# Root1_Interfaces_Test.net
KiCad netlist of a schematic drawn in EAGLE
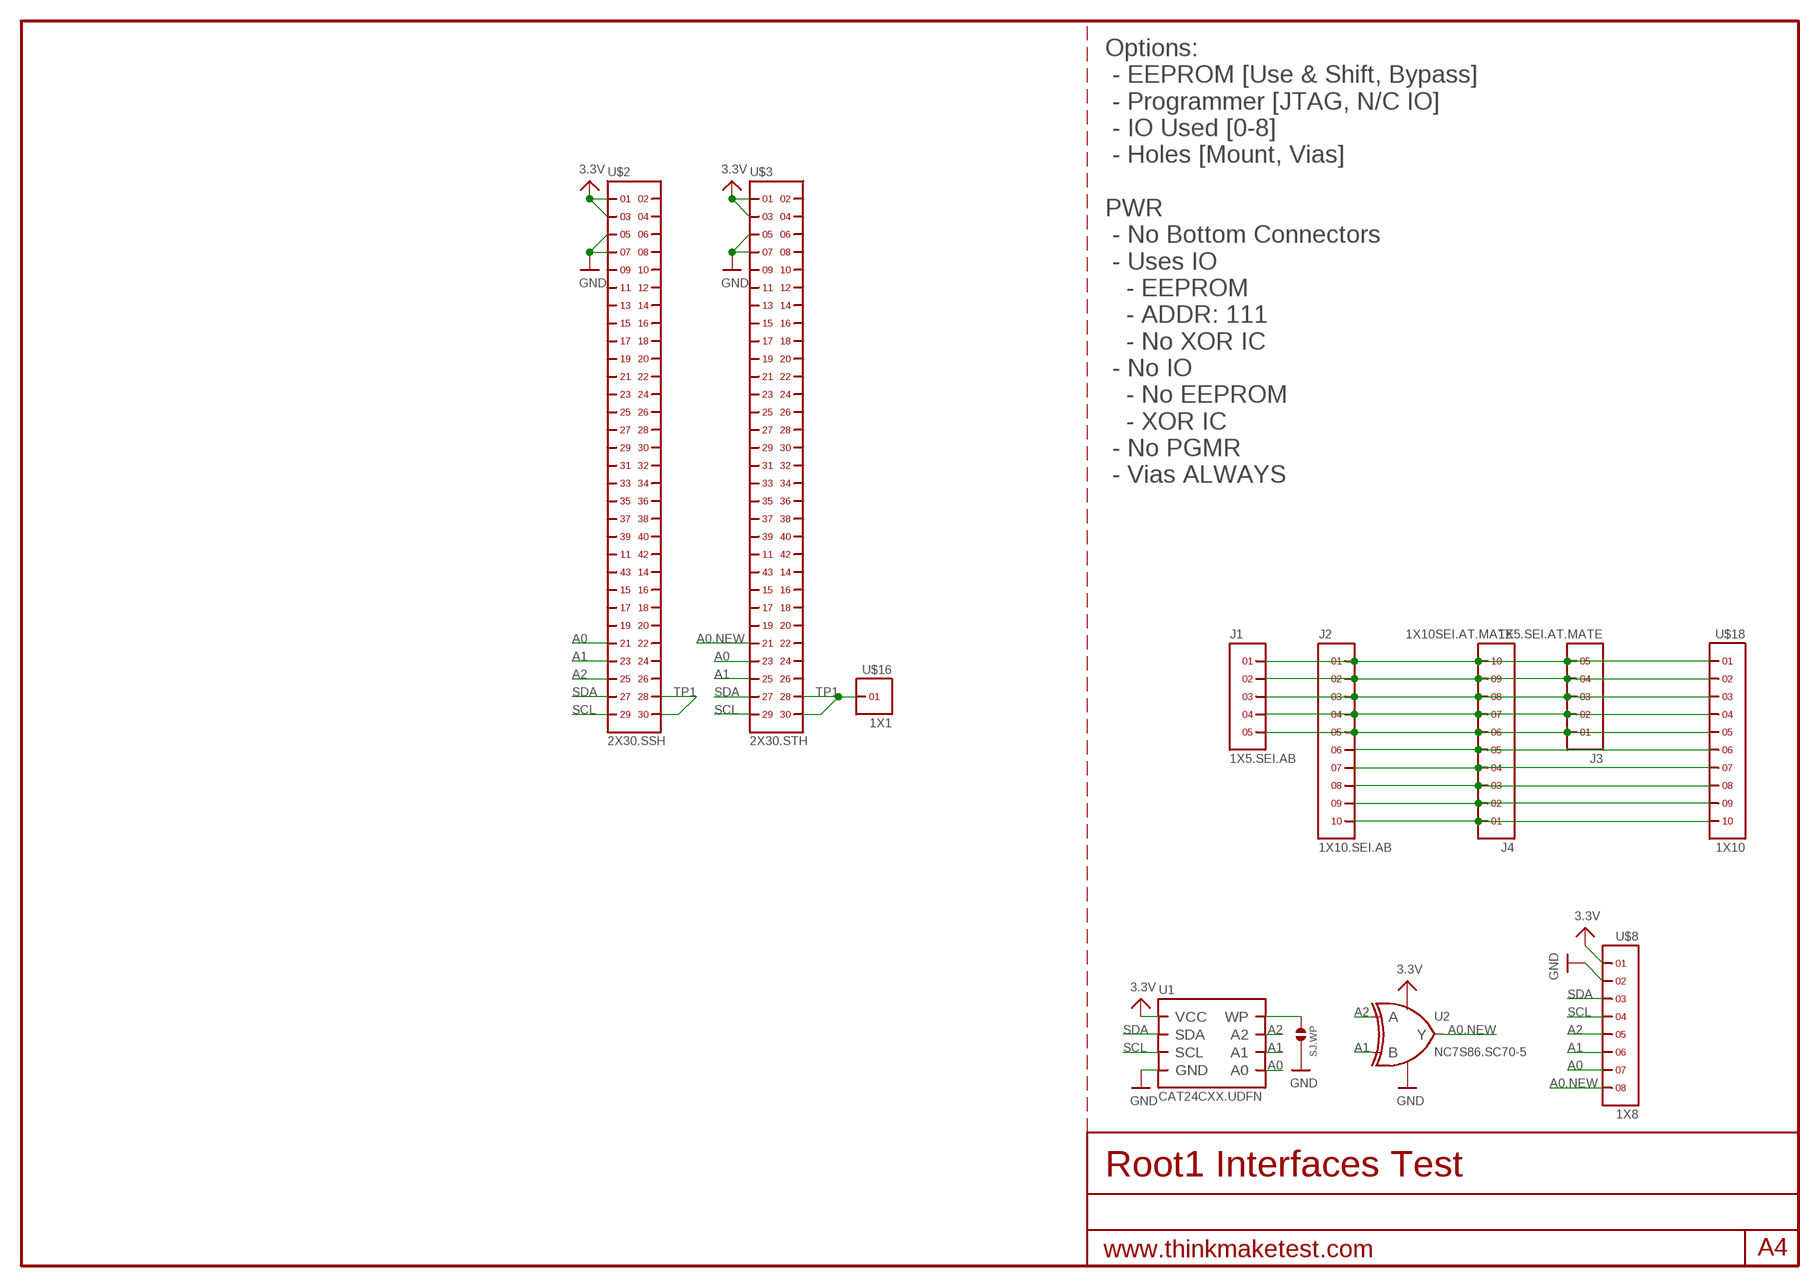
[diagram p0: schematic, sheet 1]

(export (version "E")
  (design (tool "Eeschema 10.0.6"))
  (components
    (comp (ref "J1")
      (value "1X5.SEI.AB")
      (footprint "eagle-import:SEI-105-02-XX-S-X-AB")
      (libsource (lib "eagle-import") (part "1X5.SEI.AB"))
    )
    (comp (ref "J2")
      (value "1X10.SEI.AB")
      (footprint "eagle-import:SEI-110-02-XX-S-X-AB")
      (libsource (lib "eagle-import") (part "1X10.SEI.AB"))
    )
    (comp (ref "J3")
      (value "1X5.SEI.AT.MATE")
      (footprint "eagle-import:SEI-105-02-XX-S-AT.MATE")
      (libsource (lib "eagle-import") (part "1X5.SEI.AT.MATE"))
    )
    (comp (ref "J4")
      (value "1X10SEI.AT.MATE")
      (footprint "eagle-import:SEI-110-02-XX-S-X-AT.MATE")
      (libsource (lib "eagle-import") (part "1X10SEI.AT.MATE"))
    )
    (comp (ref "SJ.WP")
      (value "SOLDERJUMPER.2.MED")
      (footprint "eagle-import:2.MED")
      (libsource (lib "eagle-import") (part "SOLDERJUMPER.2.MED"))
    )
    (comp (ref "U$2")
      (value "2X30.SSH")
      (footprint "eagle-import:SSH-030-X.XX-X-D-A")
      (libsource (lib "eagle-import") (part "2X30.SSH"))
    )
    (comp (ref "U$3")
      (value "2X30.STH")
      (footprint "eagle-import:STH-030-X.XX-X-D-A")
      (libsource (lib "eagle-import") (part "2X30.STH"))
    )
    (comp (ref "U$8")
      (value "1X8")
      (footprint "eagle-import:1X8")
      (libsource (lib "eagle-import") (part "1X8"))
    )
    (comp (ref "U$16")
      (value "1X1")
      (footprint "eagle-import:1X1")
      (libsource (lib "eagle-import") (part "1X1"))
    )
    (comp (ref "U$18")
      (value "1X10")
      (footprint "eagle-import:1X10")
      (libsource (lib "eagle-import") (part "1X10"))
    )
    (comp (ref "U1")
      (value "CAT24CXX.UDFN")
      (footprint "eagle-import:UDFN8.2X3MM")
      (libsource (lib "eagle-import") (part "CAT24CXX.UDFN"))
    )
    (comp (ref "U2")
      (value "NC7S86.SC70-5")
      (footprint "eagle-import:SC70-5")
      (libsource (lib "eagle-import") (part "NC7S86.SC70-5"))
    )
  )
  (nets
    (net (code "1") (name "/A0") (class "Default")
      (node (ref "U$2") (pin "51") (pinfunction "51_51") (pintype "bidirectional"))
      (node (ref "U$3") (pin "53") (pinfunction "53_53") (pintype "bidirectional"))
      (node (ref "U$8") (pin "7") (pinfunction "7_7") (pintype "bidirectional"))
      (node (ref "U1") (pin "1") (pinfunction "A0_1") (pintype "bidirectional"))
    )
    (net (code "2") (name "/A0.NEW") (class "Default")
      (node (ref "U$3") (pin "51") (pinfunction "51_51") (pintype "bidirectional"))
      (node (ref "U$8") (pin "8") (pinfunction "8_8") (pintype "bidirectional"))
      (node (ref "U2") (pin "4") (pinfunction "Y_4") (pintype "bidirectional"))
    )
    (net (code "3") (name "/A1") (class "Default")
      (node (ref "U$2") (pin "53") (pinfunction "53_53") (pintype "bidirectional"))
      (node (ref "U$3") (pin "55") (pinfunction "55_55") (pintype "bidirectional"))
      (node (ref "U$8") (pin "6") (pinfunction "6_6") (pintype "bidirectional"))
      (node (ref "U1") (pin "2") (pinfunction "A1_2") (pintype "bidirectional"))
      (node (ref "U2") (pin "2") (pinfunction "B_2") (pintype "bidirectional"))
    )
    (net (code "4") (name "/A2") (class "Default")
      (node (ref "U$2") (pin "55") (pinfunction "55_55") (pintype "bidirectional"))
      (node (ref "U$8") (pin "5") (pinfunction "5_5") (pintype "bidirectional"))
      (node (ref "U1") (pin "3") (pinfunction "A2_3") (pintype "bidirectional"))
      (node (ref "U2") (pin "1") (pinfunction "A_1") (pintype "bidirectional"))
    )
    (net (code "5") (name "/SCL") (class "Default")
      (node (ref "U$2") (pin "59") (pinfunction "59_59") (pintype "bidirectional"))
      (node (ref "U$3") (pin "59") (pinfunction "59_59") (pintype "bidirectional"))
      (node (ref "U$8") (pin "4") (pinfunction "4_4") (pintype "bidirectional"))
      (node (ref "U1") (pin "6") (pinfunction "SCL_6") (pintype "bidirectional"))
    )
    (net (code "6") (name "/SDA") (class "Default")
      (node (ref "U$2") (pin "57") (pinfunction "57_57") (pintype "bidirectional"))
      (node (ref "U$3") (pin "57") (pinfunction "57_57") (pintype "bidirectional"))
      (node (ref "U$8") (pin "3") (pinfunction "3_3") (pintype "bidirectional"))
      (node (ref "U1") (pin "5") (pinfunction "SDA_5") (pintype "bidirectional"))
    )
    (net (code "7") (name "/TP1") (class "Default")
      (node (ref "U$16") (pin "1") (pinfunction "1_1") (pintype "bidirectional"))
      (node (ref "U$2") (pin "58") (pinfunction "58_58") (pintype "bidirectional"))
      (node (ref "U$2") (pin "60") (pinfunction "60_60") (pintype "bidirectional"))
      (node (ref "U$3") (pin "58") (pinfunction "58_58") (pintype "bidirectional"))
      (node (ref "U$3") (pin "60") (pinfunction "60_60") (pintype "bidirectional"))
    )
    (net (code "8") (name "3.3V") (class "Default")
      (node (ref "U$2") (pin "1") (pinfunction "1_1") (pintype "bidirectional"))
      (node (ref "U$2") (pin "3") (pinfunction "3_3") (pintype "bidirectional"))
      (node (ref "U$3") (pin "1") (pinfunction "1_1") (pintype "bidirectional"))
      (node (ref "U$3") (pin "3") (pinfunction "3_3") (pintype "bidirectional"))
      (node (ref "U$8") (pin "1") (pinfunction "1_1") (pintype "bidirectional"))
      (node (ref "U1") (pin "8") (pinfunction "VCC_8") (pintype "bidirectional"))
      (node (ref "U2") (pin "6") (pinfunction "VCC_6") (pintype "bidirectional"))
    )
    (net (code "9") (name "GND") (class "Default")
      (node (ref "SJ.WP") (pin "2") (pinfunction "2_2") (pintype "bidirectional"))
      (node (ref "U$2") (pin "5") (pinfunction "5_5") (pintype "bidirectional"))
      (node (ref "U$2") (pin "7") (pinfunction "7_7") (pintype "bidirectional"))
      (node (ref "U$3") (pin "5") (pinfunction "5_5") (pintype "bidirectional"))
      (node (ref "U$3") (pin "7") (pinfunction "7_7") (pintype "bidirectional"))
      (node (ref "U$8") (pin "2") (pinfunction "2_2") (pintype "bidirectional"))
      (node (ref "U1") (pin "4") (pinfunction "GND_4") (pintype "bidirectional"))
      (node (ref "U1") (pin "PAD") (pinfunction "GND_PAD") (pintype "bidirectional"))
      (node (ref "U2") (pin "3") (pinfunction "GND_3") (pintype "bidirectional"))
    )
    (net (code "10") (name "Net-(J1-Pad1)") (class "Default")
      (node (ref "J1") (pin "1") (pinfunction "1_1") (pintype "bidirectional"))
      (node (ref "J2") (pin "1") (pinfunction "1_1") (pintype "bidirectional"))
      (node (ref "J3") (pin "5") (pinfunction "5_5") (pintype "bidirectional"))
      (node (ref "J4") (pin "10") (pinfunction "10_10") (pintype "bidirectional"))
      (node (ref "U$18") (pin "1") (pinfunction "1_1") (pintype "bidirectional"))
    )
    (net (code "11") (name "Net-(J1-Pad2)") (class "Default")
      (node (ref "J1") (pin "2") (pinfunction "2_2") (pintype "bidirectional"))
      (node (ref "J2") (pin "2") (pinfunction "2_2") (pintype "bidirectional"))
      (node (ref "J3") (pin "4") (pinfunction "4_4") (pintype "bidirectional"))
      (node (ref "J4") (pin "9") (pinfunction "9_9") (pintype "bidirectional"))
      (node (ref "U$18") (pin "2") (pinfunction "2_2") (pintype "bidirectional"))
    )
    (net (code "12") (name "Net-(J1-Pad3)") (class "Default")
      (node (ref "J1") (pin "3") (pinfunction "3_3") (pintype "bidirectional"))
      (node (ref "J2") (pin "3") (pinfunction "3_3") (pintype "bidirectional"))
      (node (ref "J3") (pin "3") (pinfunction "3_3") (pintype "bidirectional"))
      (node (ref "J4") (pin "8") (pinfunction "8_8") (pintype "bidirectional"))
      (node (ref "U$18") (pin "3") (pinfunction "3_3") (pintype "bidirectional"))
    )
    (net (code "13") (name "Net-(J1-Pad4)") (class "Default")
      (node (ref "J1") (pin "4") (pinfunction "4_4") (pintype "bidirectional"))
      (node (ref "J2") (pin "4") (pinfunction "4_4") (pintype "bidirectional"))
      (node (ref "J3") (pin "2") (pinfunction "2_2") (pintype "bidirectional"))
      (node (ref "J4") (pin "7") (pinfunction "7_7") (pintype "bidirectional"))
      (node (ref "U$18") (pin "4") (pinfunction "4_4") (pintype "bidirectional"))
    )
    (net (code "14") (name "Net-(J1-Pad5)") (class "Default")
      (node (ref "J1") (pin "5") (pinfunction "5_5") (pintype "bidirectional"))
      (node (ref "J2") (pin "5") (pinfunction "5_5") (pintype "bidirectional"))
      (node (ref "J3") (pin "1") (pinfunction "1_1") (pintype "bidirectional"))
      (node (ref "J4") (pin "6") (pinfunction "6_6") (pintype "bidirectional"))
      (node (ref "U$18") (pin "5") (pinfunction "5_5") (pintype "bidirectional"))
    )
    (net (code "15") (name "Net-(J2-Pad6)") (class "Default")
      (node (ref "J2") (pin "6") (pinfunction "6_6") (pintype "bidirectional"))
      (node (ref "J4") (pin "5") (pinfunction "5_5") (pintype "bidirectional"))
      (node (ref "U$18") (pin "6") (pinfunction "6_6") (pintype "bidirectional"))
    )
    (net (code "16") (name "Net-(J2-Pad7)") (class "Default")
      (node (ref "J2") (pin "7") (pinfunction "7_7") (pintype "bidirectional"))
      (node (ref "J4") (pin "4") (pinfunction "4_4") (pintype "bidirectional"))
      (node (ref "U$18") (pin "7") (pinfunction "7_7") (pintype "bidirectional"))
    )
    (net (code "17") (name "Net-(J2-Pad8)") (class "Default")
      (node (ref "J2") (pin "8") (pinfunction "8_8") (pintype "bidirectional"))
      (node (ref "J4") (pin "3") (pinfunction "3_3") (pintype "bidirectional"))
      (node (ref "U$18") (pin "8") (pinfunction "8_8") (pintype "bidirectional"))
    )
    (net (code "18") (name "Net-(J2-Pad9)") (class "Default")
      (node (ref "J2") (pin "9") (pinfunction "9_9") (pintype "bidirectional"))
      (node (ref "J4") (pin "2") (pinfunction "2_2") (pintype "bidirectional"))
      (node (ref "U$18") (pin "9") (pinfunction "9_9") (pintype "bidirectional"))
    )
    (net (code "19") (name "Net-(J2-Pad10)") (class "Default")
      (node (ref "J2") (pin "10") (pinfunction "10_10") (pintype "bidirectional"))
      (node (ref "J4") (pin "1") (pinfunction "1_1") (pintype "bidirectional"))
      (node (ref "U$18") (pin "10") (pinfunction "10_10") (pintype "bidirectional"))
    )
    (net (code "20") (name "Net-(U1-WP)") (class "Default")
      (node (ref "SJ.WP") (pin "1") (pinfunction "1_1") (pintype "bidirectional"))
      (node (ref "U1") (pin "7") (pinfunction "WP_7") (pintype "bidirectional"))
    )
    (net (code "21") (name "unconnected-(U$2-Pad2)") (class "Default")
      (node (ref "U$2") (pin "2") (pinfunction "2_2") (pintype "bidirectional"))
    )
    (net (code "22") (name "unconnected-(U$2-Pad4)") (class "Default")
      (node (ref "U$2") (pin "4") (pinfunction "4_4") (pintype "bidirectional"))
    )
    (net (code "23") (name "unconnected-(U$2-Pad6)") (class "Default")
      (node (ref "U$2") (pin "6") (pinfunction "6_6") (pintype "bidirectional"))
    )
    (net (code "24") (name "unconnected-(U$2-Pad8)") (class "Default")
      (node (ref "U$2") (pin "8") (pinfunction "8_8") (pintype "bidirectional"))
    )
    (net (code "25") (name "unconnected-(U$2-Pad9)") (class "Default")
      (node (ref "U$2") (pin "9") (pinfunction "9_9") (pintype "bidirectional"))
    )
    (net (code "26") (name "unconnected-(U$2-Pad10)") (class "Default")
      (node (ref "U$2") (pin "10") (pinfunction "10_10") (pintype "bidirectional"))
    )
    (net (code "27") (name "unconnected-(U$2-Pad11)") (class "Default")
      (node (ref "U$2") (pin "11") (pinfunction "11_11") (pintype "bidirectional"))
    )
    (net (code "28") (name "unconnected-(U$2-Pad12)") (class "Default")
      (node (ref "U$2") (pin "12") (pinfunction "12_12") (pintype "bidirectional"))
    )
    (net (code "29") (name "unconnected-(U$2-Pad13)") (class "Default")
      (node (ref "U$2") (pin "13") (pinfunction "13_13") (pintype "bidirectional"))
    )
    (net (code "30") (name "unconnected-(U$2-Pad14)") (class "Default")
      (node (ref "U$2") (pin "14") (pinfunction "14_14") (pintype "bidirectional"))
    )
    (net (code "31") (name "unconnected-(U$2-Pad15)") (class "Default")
      (node (ref "U$2") (pin "15") (pinfunction "15_15") (pintype "bidirectional"))
    )
    (net (code "32") (name "unconnected-(U$2-Pad16)") (class "Default")
      (node (ref "U$2") (pin "16") (pinfunction "16_16") (pintype "bidirectional"))
    )
    (net (code "33") (name "unconnected-(U$2-Pad17)") (class "Default")
      (node (ref "U$2") (pin "17") (pinfunction "17_17") (pintype "bidirectional"))
    )
    (net (code "34") (name "unconnected-(U$2-Pad18)") (class "Default")
      (node (ref "U$2") (pin "18") (pinfunction "18_18") (pintype "bidirectional"))
    )
    (net (code "35") (name "unconnected-(U$2-Pad19)") (class "Default")
      (node (ref "U$2") (pin "19") (pinfunction "19_19") (pintype "bidirectional"))
    )
    (net (code "36") (name "unconnected-(U$2-Pad20)") (class "Default")
      (node (ref "U$2") (pin "20") (pinfunction "20_20") (pintype "bidirectional"))
    )
    (net (code "37") (name "unconnected-(U$2-Pad21)") (class "Default")
      (node (ref "U$2") (pin "21") (pinfunction "21_21") (pintype "bidirectional"))
    )
    (net (code "38") (name "unconnected-(U$2-Pad22)") (class "Default")
      (node (ref "U$2") (pin "22") (pinfunction "22_22") (pintype "bidirectional"))
    )
    (net (code "39") (name "unconnected-(U$2-Pad23)") (class "Default")
      (node (ref "U$2") (pin "23") (pinfunction "23_23") (pintype "bidirectional"))
    )
    (net (code "40") (name "unconnected-(U$2-Pad24)") (class "Default")
      (node (ref "U$2") (pin "24") (pinfunction "24_24") (pintype "bidirectional"))
    )
    (net (code "41") (name "unconnected-(U$2-Pad25)") (class "Default")
      (node (ref "U$2") (pin "25") (pinfunction "25_25") (pintype "bidirectional"))
    )
    (net (code "42") (name "unconnected-(U$2-Pad26)") (class "Default")
      (node (ref "U$2") (pin "26") (pinfunction "26_26") (pintype "bidirectional"))
    )
    (net (code "43") (name "unconnected-(U$2-Pad27)") (class "Default")
      (node (ref "U$2") (pin "27") (pinfunction "27_27") (pintype "bidirectional"))
    )
    (net (code "44") (name "unconnected-(U$2-Pad28)") (class "Default")
      (node (ref "U$2") (pin "28") (pinfunction "28_28") (pintype "bidirectional"))
    )
    (net (code "45") (name "unconnected-(U$2-Pad29)") (class "Default")
      (node (ref "U$2") (pin "29") (pinfunction "29_29") (pintype "bidirectional"))
    )
    (net (code "46") (name "unconnected-(U$2-Pad30)") (class "Default")
      (node (ref "U$2") (pin "30") (pinfunction "30_30") (pintype "bidirectional"))
    )
    (net (code "47") (name "unconnected-(U$2-Pad31)") (class "Default")
      (node (ref "U$2") (pin "31") (pinfunction "31_31") (pintype "bidirectional"))
    )
    (net (code "48") (name "unconnected-(U$2-Pad32)") (class "Default")
      (node (ref "U$2") (pin "32") (pinfunction "32_32") (pintype "bidirectional"))
    )
    (net (code "49") (name "unconnected-(U$2-Pad33)") (class "Default")
      (node (ref "U$2") (pin "33") (pinfunction "33_33") (pintype "bidirectional"))
    )
    (net (code "50") (name "unconnected-(U$2-Pad34)") (class "Default")
      (node (ref "U$2") (pin "34") (pinfunction "34_34") (pintype "bidirectional"))
    )
    (net (code "51") (name "unconnected-(U$2-Pad35)") (class "Default")
      (node (ref "U$2") (pin "35") (pinfunction "35_35") (pintype "bidirectional"))
    )
    (net (code "52") (name "unconnected-(U$2-Pad36)") (class "Default")
      (node (ref "U$2") (pin "36") (pinfunction "36_36") (pintype "bidirectional"))
    )
    (net (code "53") (name "unconnected-(U$2-Pad37)") (class "Default")
      (node (ref "U$2") (pin "37") (pinfunction "37_37") (pintype "bidirectional"))
    )
    (net (code "54") (name "unconnected-(U$2-Pad38)") (class "Default")
      (node (ref "U$2") (pin "38") (pinfunction "38_38") (pintype "bidirectional"))
    )
    (net (code "55") (name "unconnected-(U$2-Pad39)") (class "Default")
      (node (ref "U$2") (pin "39") (pinfunction "39_39") (pintype "bidirectional"))
    )
    (net (code "56") (name "unconnected-(U$2-Pad40)") (class "Default")
      (node (ref "U$2") (pin "40") (pinfunction "40_40") (pintype "bidirectional"))
    )
    (net (code "57") (name "unconnected-(U$2-Pad41)") (class "Default")
      (node (ref "U$2") (pin "41") (pinfunction "41_41") (pintype "bidirectional"))
    )
    (net (code "58") (name "unconnected-(U$2-Pad42)") (class "Default")
      (node (ref "U$2") (pin "42") (pinfunction "42_42") (pintype "bidirectional"))
    )
    (net (code "59") (name "unconnected-(U$2-Pad43)") (class "Default")
      (node (ref "U$2") (pin "43") (pinfunction "43_43") (pintype "bidirectional"))
    )
    (net (code "60") (name "unconnected-(U$2-Pad44)") (class "Default")
      (node (ref "U$2") (pin "44") (pinfunction "44_44") (pintype "bidirectional"))
    )
    (net (code "61") (name "unconnected-(U$2-Pad45)") (class "Default")
      (node (ref "U$2") (pin "45") (pinfunction "45_45") (pintype "bidirectional"))
    )
    (net (code "62") (name "unconnected-(U$2-Pad46)") (class "Default")
      (node (ref "U$2") (pin "46") (pinfunction "46_46") (pintype "bidirectional"))
    )
    (net (code "63") (name "unconnected-(U$2-Pad47)") (class "Default")
      (node (ref "U$2") (pin "47") (pinfunction "47_47") (pintype "bidirectional"))
    )
    (net (code "64") (name "unconnected-(U$2-Pad48)") (class "Default")
      (node (ref "U$2") (pin "48") (pinfunction "48_48") (pintype "bidirectional"))
    )
    (net (code "65") (name "unconnected-(U$2-Pad49)") (class "Default")
      (node (ref "U$2") (pin "49") (pinfunction "49_49") (pintype "bidirectional"))
    )
    (net (code "66") (name "unconnected-(U$2-Pad50)") (class "Default")
      (node (ref "U$2") (pin "50") (pinfunction "50_50") (pintype "bidirectional"))
    )
    (net (code "67") (name "unconnected-(U$2-Pad52)") (class "Default")
      (node (ref "U$2") (pin "52") (pinfunction "52_52") (pintype "bidirectional"))
    )
    (net (code "68") (name "unconnected-(U$2-Pad54)") (class "Default")
      (node (ref "U$2") (pin "54") (pinfunction "54_54") (pintype "bidirectional"))
    )
    (net (code "69") (name "unconnected-(U$2-Pad56)") (class "Default")
      (node (ref "U$2") (pin "56") (pinfunction "56_56") (pintype "bidirectional"))
    )
    (net (code "70") (name "unconnected-(U$3-Pad2)") (class "Default")
      (node (ref "U$3") (pin "2") (pinfunction "2_2") (pintype "bidirectional"))
    )
    (net (code "71") (name "unconnected-(U$3-Pad4)") (class "Default")
      (node (ref "U$3") (pin "4") (pinfunction "4_4") (pintype "bidirectional"))
    )
    (net (code "72") (name "unconnected-(U$3-Pad6)") (class "Default")
      (node (ref "U$3") (pin "6") (pinfunction "6_6") (pintype "bidirectional"))
    )
    (net (code "73") (name "unconnected-(U$3-Pad8)") (class "Default")
      (node (ref "U$3") (pin "8") (pinfunction "8_8") (pintype "bidirectional"))
    )
    (net (code "74") (name "unconnected-(U$3-Pad9)") (class "Default")
      (node (ref "U$3") (pin "9") (pinfunction "9_9") (pintype "bidirectional"))
    )
    (net (code "75") (name "unconnected-(U$3-Pad10)") (class "Default")
      (node (ref "U$3") (pin "10") (pinfunction "10_10") (pintype "bidirectional"))
    )
    (net (code "76") (name "unconnected-(U$3-Pad11)") (class "Default")
      (node (ref "U$3") (pin "11") (pinfunction "11_11") (pintype "bidirectional"))
    )
    (net (code "77") (name "unconnected-(U$3-Pad12)") (class "Default")
      (node (ref "U$3") (pin "12") (pinfunction "12_12") (pintype "bidirectional"))
    )
    (net (code "78") (name "unconnected-(U$3-Pad13)") (class "Default")
      (node (ref "U$3") (pin "13") (pinfunction "13_13") (pintype "bidirectional"))
    )
    (net (code "79") (name "unconnected-(U$3-Pad14)") (class "Default")
      (node (ref "U$3") (pin "14") (pinfunction "14_14") (pintype "bidirectional"))
    )
    (net (code "80") (name "unconnected-(U$3-Pad15)") (class "Default")
      (node (ref "U$3") (pin "15") (pinfunction "15_15") (pintype "bidirectional"))
    )
    (net (code "81") (name "unconnected-(U$3-Pad16)") (class "Default")
      (node (ref "U$3") (pin "16") (pinfunction "16_16") (pintype "bidirectional"))
    )
    (net (code "82") (name "unconnected-(U$3-Pad17)") (class "Default")
      (node (ref "U$3") (pin "17") (pinfunction "17_17") (pintype "bidirectional"))
    )
    (net (code "83") (name "unconnected-(U$3-Pad18)") (class "Default")
      (node (ref "U$3") (pin "18") (pinfunction "18_18") (pintype "bidirectional"))
    )
    (net (code "84") (name "unconnected-(U$3-Pad19)") (class "Default")
      (node (ref "U$3") (pin "19") (pinfunction "19_19") (pintype "bidirectional"))
    )
    (net (code "85") (name "unconnected-(U$3-Pad20)") (class "Default")
      (node (ref "U$3") (pin "20") (pinfunction "20_20") (pintype "bidirectional"))
    )
    (net (code "86") (name "unconnected-(U$3-Pad21)") (class "Default")
      (node (ref "U$3") (pin "21") (pinfunction "21_21") (pintype "bidirectional"))
    )
    (net (code "87") (name "unconnected-(U$3-Pad22)") (class "Default")
      (node (ref "U$3") (pin "22") (pinfunction "22_22") (pintype "bidirectional"))
    )
    (net (code "88") (name "unconnected-(U$3-Pad23)") (class "Default")
      (node (ref "U$3") (pin "23") (pinfunction "23_23") (pintype "bidirectional"))
    )
    (net (code "89") (name "unconnected-(U$3-Pad24)") (class "Default")
      (node (ref "U$3") (pin "24") (pinfunction "24_24") (pintype "bidirectional"))
    )
    (net (code "90") (name "unconnected-(U$3-Pad25)") (class "Default")
      (node (ref "U$3") (pin "25") (pinfunction "25_25") (pintype "bidirectional"))
    )
    (net (code "91") (name "unconnected-(U$3-Pad26)") (class "Default")
      (node (ref "U$3") (pin "26") (pinfunction "26_26") (pintype "bidirectional"))
    )
    (net (code "92") (name "unconnected-(U$3-Pad27)") (class "Default")
      (node (ref "U$3") (pin "27") (pinfunction "27_27") (pintype "bidirectional"))
    )
    (net (code "93") (name "unconnected-(U$3-Pad28)") (class "Default")
      (node (ref "U$3") (pin "28") (pinfunction "28_28") (pintype "bidirectional"))
    )
    (net (code "94") (name "unconnected-(U$3-Pad29)") (class "Default")
      (node (ref "U$3") (pin "29") (pinfunction "29_29") (pintype "bidirectional"))
    )
    (net (code "95") (name "unconnected-(U$3-Pad30)") (class "Default")
      (node (ref "U$3") (pin "30") (pinfunction "30_30") (pintype "bidirectional"))
    )
    (net (code "96") (name "unconnected-(U$3-Pad31)") (class "Default")
      (node (ref "U$3") (pin "31") (pinfunction "31_31") (pintype "bidirectional"))
    )
    (net (code "97") (name "unconnected-(U$3-Pad32)") (class "Default")
      (node (ref "U$3") (pin "32") (pinfunction "32_32") (pintype "bidirectional"))
    )
    (net (code "98") (name "unconnected-(U$3-Pad33)") (class "Default")
      (node (ref "U$3") (pin "33") (pinfunction "33_33") (pintype "bidirectional"))
    )
    (net (code "99") (name "unconnected-(U$3-Pad34)") (class "Default")
      (node (ref "U$3") (pin "34") (pinfunction "34_34") (pintype "bidirectional"))
    )
    (net (code "100") (name "unconnected-(U$3-Pad35)") (class "Default")
      (node (ref "U$3") (pin "35") (pinfunction "35_35") (pintype "bidirectional"))
    )
    (net (code "101") (name "unconnected-(U$3-Pad36)") (class "Default")
      (node (ref "U$3") (pin "36") (pinfunction "36_36") (pintype "bidirectional"))
    )
    (net (code "102") (name "unconnected-(U$3-Pad37)") (class "Default")
      (node (ref "U$3") (pin "37") (pinfunction "37_37") (pintype "bidirectional"))
    )
    (net (code "103") (name "unconnected-(U$3-Pad38)") (class "Default")
      (node (ref "U$3") (pin "38") (pinfunction "38_38") (pintype "bidirectional"))
    )
    (net (code "104") (name "unconnected-(U$3-Pad39)") (class "Default")
      (node (ref "U$3") (pin "39") (pinfunction "39_39") (pintype "bidirectional"))
    )
    (net (code "105") (name "unconnected-(U$3-Pad40)") (class "Default")
      (node (ref "U$3") (pin "40") (pinfunction "40_40") (pintype "bidirectional"))
    )
    (net (code "106") (name "unconnected-(U$3-Pad41)") (class "Default")
      (node (ref "U$3") (pin "41") (pinfunction "41_41") (pintype "bidirectional"))
    )
    (net (code "107") (name "unconnected-(U$3-Pad42)") (class "Default")
      (node (ref "U$3") (pin "42") (pinfunction "42_42") (pintype "bidirectional"))
    )
    (net (code "108") (name "unconnected-(U$3-Pad43)") (class "Default")
      (node (ref "U$3") (pin "43") (pinfunction "43_43") (pintype "bidirectional"))
    )
    (net (code "109") (name "unconnected-(U$3-Pad44)") (class "Default")
      (node (ref "U$3") (pin "44") (pinfunction "44_44") (pintype "bidirectional"))
    )
    (net (code "110") (name "unconnected-(U$3-Pad45)") (class "Default")
      (node (ref "U$3") (pin "45") (pinfunction "45_45") (pintype "bidirectional"))
    )
    (net (code "111") (name "unconnected-(U$3-Pad46)") (class "Default")
      (node (ref "U$3") (pin "46") (pinfunction "46_46") (pintype "bidirectional"))
    )
    (net (code "112") (name "unconnected-(U$3-Pad47)") (class "Default")
      (node (ref "U$3") (pin "47") (pinfunction "47_47") (pintype "bidirectional"))
    )
    (net (code "113") (name "unconnected-(U$3-Pad48)") (class "Default")
      (node (ref "U$3") (pin "48") (pinfunction "48_48") (pintype "bidirectional"))
    )
    (net (code "114") (name "unconnected-(U$3-Pad49)") (class "Default")
      (node (ref "U$3") (pin "49") (pinfunction "49_49") (pintype "bidirectional"))
    )
    (net (code "115") (name "unconnected-(U$3-Pad50)") (class "Default")
      (node (ref "U$3") (pin "50") (pinfunction "50_50") (pintype "bidirectional"))
    )
    (net (code "116") (name "unconnected-(U$3-Pad52)") (class "Default")
      (node (ref "U$3") (pin "52") (pinfunction "52_52") (pintype "bidirectional"))
    )
    (net (code "117") (name "unconnected-(U$3-Pad54)") (class "Default")
      (node (ref "U$3") (pin "54") (pinfunction "54_54") (pintype "bidirectional"))
    )
    (net (code "118") (name "unconnected-(U$3-Pad56)") (class "Default")
      (node (ref "U$3") (pin "56") (pinfunction "56_56") (pintype "bidirectional"))
    )
  )
)
